# 04_-_CPU_-_PCIE_USB.net
KiCad netlist of a schematic drawn in Altium Designer
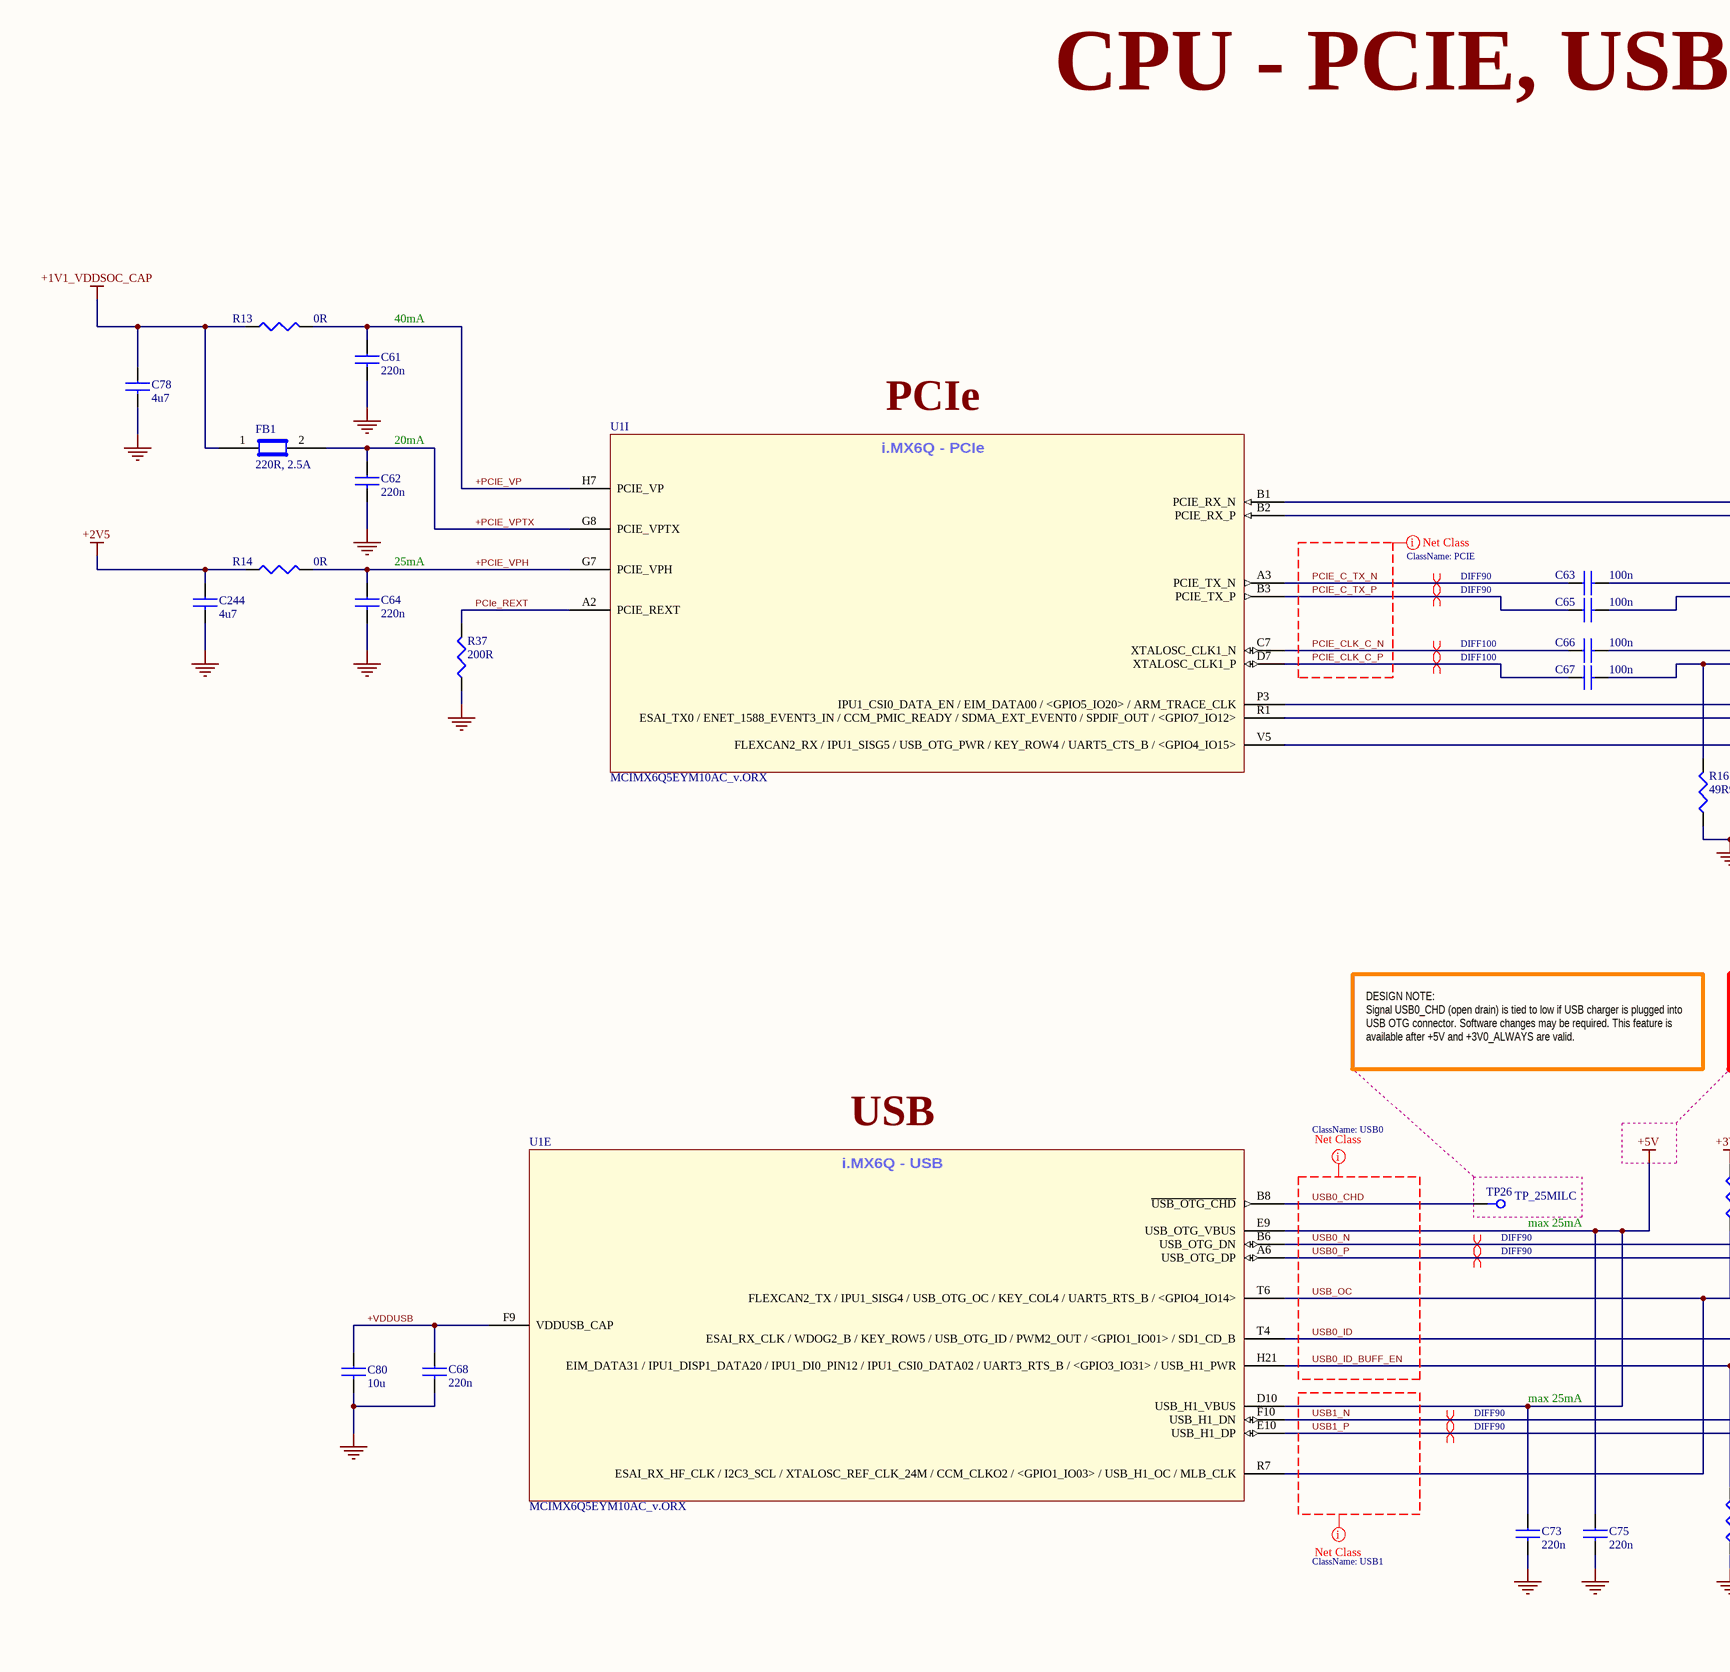
[diagram p0: [04] - CPU - PCIE, USB.SchDoc, left]
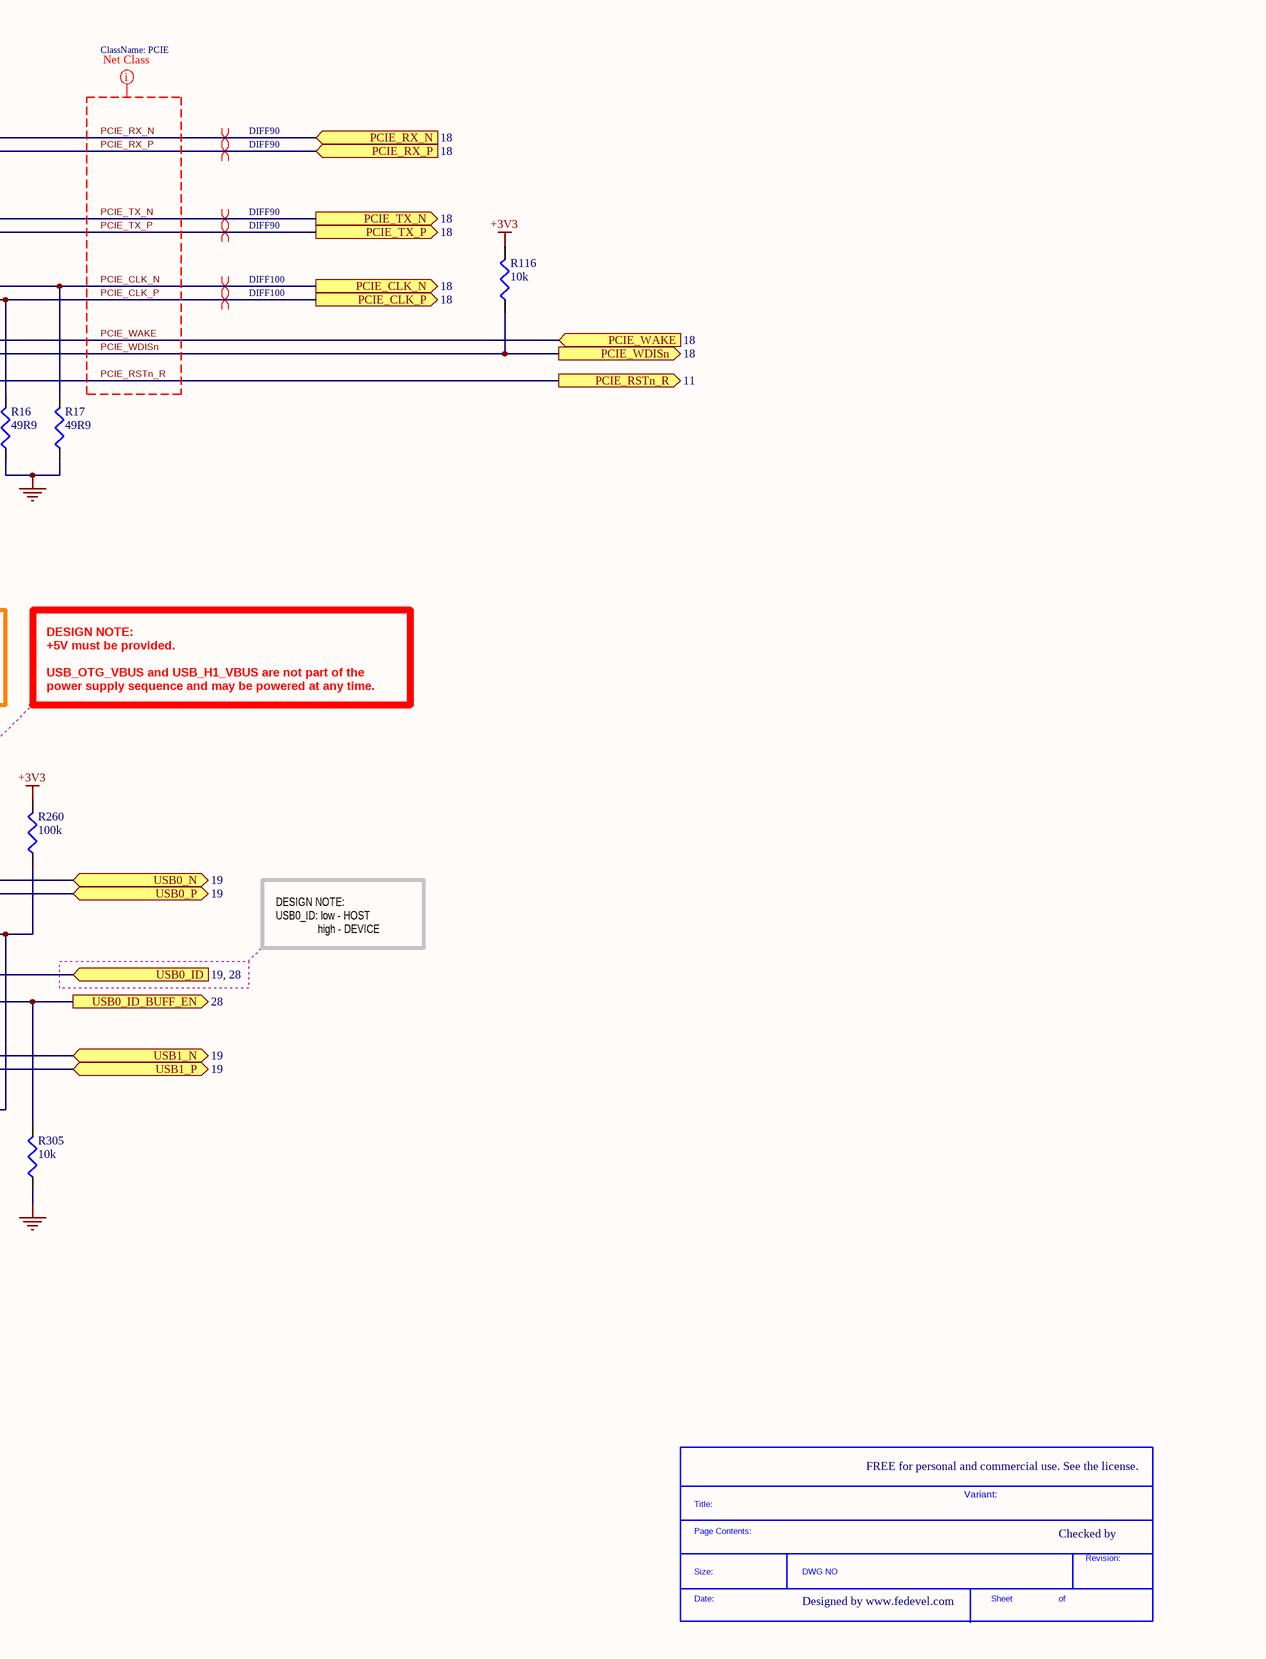
[diagram p1: [04] - CPU - PCIE, USB.SchDoc, right]

(export (version "E")
  (design (tool "Eeschema 10.0.6"))
  (components
    (comp (ref "C61")
      (value "220n")
      (footprint "C0201")
      (description "CAP CER 0.22UF 6.3V 20% X5R 0201")
      (fields
        (field (name "MANUFACTURER") "TDK Corporation")
        (field (name "MANUFACTURER PART NUMBER") "C0603X5R0J224M030BB")
        (field (name ".CHECKED PCB") "MM")
        (field (name ".CHECKED SCH") "MM")
        (field (name ".CREATOR") "MM")
      )
      (libsource (lib "Integrated_Library_FEDEVEL_0201") (part "C0603X5R0J224M030BB"))
    )
    (comp (ref "C62")
      (value "220n")
      (footprint "C0201")
      (description "CAP CER 0.22UF 6.3V 20% X5R 0201")
      (fields
        (field (name "MANUFACTURER") "TDK Corporation")
        (field (name "MANUFACTURER PART NUMBER") "C0603X5R0J224M030BB")
        (field (name ".CHECKED PCB") "MM")
        (field (name ".CHECKED SCH") "MM")
        (field (name ".CREATOR") "MM")
      )
      (libsource (lib "Integrated_Library_FEDEVEL_0201") (part "C0603X5R0J224M030BB"))
    )
    (comp (ref "C63")
      (value "100n")
      (footprint "C0402")
      (description "CAP CER .10UF 50V X5R 10% 0402")
      (fields
        (field (name "MANUFACTURER") "TDK Corporation")
        (field (name "MANUFACTURER PART NUMBER") "C1005X5R1H104K")
      )
      (libsource (lib "Integrated_Library_FEDEVEL_APR_2015") (part "C1005X5R1H104K"))
    )
    (comp (ref "C64")
      (value "220n")
      (footprint "C0201")
      (description "CAP CER 0.22UF 6.3V 20% X5R 0201")
      (fields
        (field (name "MANUFACTURER") "TDK Corporation")
        (field (name "MANUFACTURER PART NUMBER") "C0603X5R0J224M030BB")
        (field (name ".CHECKED PCB") "MM")
        (field (name ".CHECKED SCH") "MM")
        (field (name ".CREATOR") "MM")
      )
      (libsource (lib "Integrated_Library_FEDEVEL_0201") (part "C0603X5R0J224M030BB"))
    )
    (comp (ref "C65")
      (value "100n")
      (footprint "C0402")
      (description "CAP CER .10UF 50V X5R 10% 0402")
      (fields
        (field (name "MANUFACTURER") "TDK Corporation")
        (field (name "MANUFACTURER PART NUMBER") "C1005X5R1H104K")
      )
      (libsource (lib "Integrated_Library_FEDEVEL_APR_2015") (part "C1005X5R1H104K"))
    )
    (comp (ref "C66")
      (value "100n")
      (footprint "C0402")
      (description "CAP CER .10UF 50V X5R 10% 0402")
      (fields
        (field (name "MANUFACTURER") "TDK Corporation")
        (field (name "MANUFACTURER PART NUMBER") "C1005X5R1H104K")
      )
      (libsource (lib "Integrated_Library_FEDEVEL_APR_2015") (part "C1005X5R1H104K"))
    )
    (comp (ref "C67")
      (value "100n")
      (footprint "C0402")
      (description "CAP CER .10UF 50V X5R 10% 0402")
      (fields
        (field (name "MANUFACTURER") "TDK Corporation")
        (field (name "MANUFACTURER PART NUMBER") "C1005X5R1H104K")
      )
      (libsource (lib "Integrated_Library_FEDEVEL_APR_2015") (part "C1005X5R1H104K"))
    )
    (comp (ref "C68")
      (value "220n")
      (footprint "C0201")
      (description "CAP CER 0.22UF 6.3V 20% X5R 0201")
      (fields
        (field (name "MANUFACTURER") "TDK Corporation")
        (field (name "MANUFACTURER PART NUMBER") "C0603X5R0J224M030BB")
        (field (name ".CHECKED PCB") "MM")
        (field (name ".CHECKED SCH") "MM")
        (field (name ".CREATOR") "MM")
      )
      (libsource (lib "Integrated_Library_FEDEVEL_0201") (part "C0603X5R0J224M030BB"))
    )
    (comp (ref "C73")
      (value "220n")
      (footprint "C0201")
      (description "CAP CER 0.22UF 6.3V 20% X5R 0201")
      (fields
        (field (name "MANUFACTURER") "TDK Corporation")
        (field (name "MANUFACTURER PART NUMBER") "C0603X5R0J224M030BB")
        (field (name ".CHECKED PCB") "MM")
        (field (name ".CHECKED SCH") "MM")
        (field (name ".CREATOR") "MM")
      )
      (libsource (lib "Integrated_Library_FEDEVEL_0201") (part "C0603X5R0J224M030BB"))
    )
    (comp (ref "C75")
      (value "220n")
      (footprint "C0201")
      (description "CAP CER 0.22UF 6.3V 20% X5R 0201")
      (fields
        (field (name "MANUFACTURER") "TDK Corporation")
        (field (name "MANUFACTURER PART NUMBER") "C0603X5R0J224M030BB")
        (field (name ".CHECKED PCB") "MM")
        (field (name ".CHECKED SCH") "MM")
        (field (name ".CREATOR") "MM")
      )
      (libsource (lib "Integrated_Library_FEDEVEL_0201") (part "C0603X5R0J224M030BB"))
    )
    (comp (ref "C78")
      (value "4u7")
      (footprint "C0402")
      (description "CAP CER 4.7UF 10V 20% X5R 0402")
      (fields
        (field (name "MANUFACTURER") "TDK Corporation")
        (field (name "MANUFACTURER PART NUMBER") "C1005X5R1A475M")
      )
      (libsource (lib "Integrated_Library_FEDEVEL_APR_2015") (part "C1005X5R1A475M"))
    )
    (comp (ref "C80")
      (value "10u")
      (footprint "C0603")
      (description "CAP CER 10UF 6.3V X5R 20% 0603")
      (fields
        (field (name "MANUFACTURER") "TDK Corporation")
        (field (name "MANUFACTURER PART NUMBER") "C1608X5R0J106M")
      )
      (libsource (lib "Integrated_Library_FEDEVEL_APR_2015") (part "C1608X5R0J106M"))
    )
    (comp (ref "C244")
      (value "4u7")
      (footprint "C0402")
      (description "CAP CER 4.7UF 10V 20% X5R 0402")
      (fields
        (field (name "MANUFACTURER") "TDK Corporation")
        (field (name "MANUFACTURER PART NUMBER") "C1005X5R1A475M")
      )
      (libsource (lib "Integrated_Library_FEDEVEL_APR_2015") (part "C1005X5R1A475M"))
    )
    (comp (ref "FB1")
      (value "220R, 2.5A")
      (footprint "C0603")
      (description "FERRITE CHIP 220 OHM 2500MA 0603")
      (fields
        (field (name "MANUFACTURER") "Murata Electronics North America")
        (field (name "MANUFACTURER PART NUMBER") "BLM18SG221TN1D")
      )
      (libsource (lib "Integrated_Library_FEDEVEL_APR_2015") (part "BLM18SG221TN1D"))
    )
    (comp (ref "R13")
      (value "0R")
      (footprint "R0402")
      (description "RES 0.0 OHM 1/16W 0402 SMD")
      (fields
        (field (name "MANUFACTURER") "Yageo")
        (field (name "MANUFACTURER PART NUMBER") "RC0402JR-070RL")
      )
      (libsource (lib "Integrated_Library_FEDEVEL_APR_2015") (part "RC0402JR-070RL"))
    )
    (comp (ref "R14")
      (value "0R")
      (footprint "R0402")
      (description "RES 0.0 OHM 1/16W 0402 SMD")
      (fields
        (field (name "MANUFACTURER") "Yageo")
        (field (name "MANUFACTURER PART NUMBER") "RC0402JR-070RL")
      )
      (libsource (lib "Integrated_Library_FEDEVEL_APR_2015") (part "RC0402JR-070RL"))
    )
    (comp (ref "R16")
      (value "49R9")
      (footprint "R0402")
      (description "RES 49.9 OHM 1/16W 1% 0402 SMD")
      (fields
        (field (name "MANUFACTURER") "Yageo")
        (field (name "MANUFACTURER PART NUMBER") "RC0402FR-0749R9L")
      )
      (libsource (lib "Integrated_Library_FEDEVEL_APR_2015") (part "RC0402FR-0749R9L"))
    )
    (comp (ref "R17")
      (value "49R9")
      (footprint "R0402")
      (description "RES 49.9 OHM 1/16W 1% 0402 SMD")
      (fields
        (field (name "MANUFACTURER") "Yageo")
        (field (name "MANUFACTURER PART NUMBER") "RC0402FR-0749R9L")
      )
      (libsource (lib "Integrated_Library_FEDEVEL_APR_2015") (part "RC0402FR-0749R9L"))
    )
    (comp (ref "R37")
      (value "200R")
      (footprint "R0402")
      (description "RES 200 OHM 1/16W 1% 0402 SMD")
      (fields
        (field (name "MANUFACTURER") "Vishay Dale")
        (field (name "MANUFACTURER PART NUMBER") "CRCW0402200RFKED")
        (field (name ".CREATOR") "MM")
      )
      (libsource (lib "Integrated_Library_FEDEVEL_APR_2015") (part "CRCW0402200RFKED"))
    )
    (comp (ref "R116")
      (value "10k")
      (footprint "R0402")
      (description "RES 10.0K OHM 1/16W 1% 0402 SMD")
      (fields
        (field (name "MANUFACTURER") "Yageo")
        (field (name "MANUFACTURER PART NUMBER") "RC0402FR-0710KL")
      )
      (libsource (lib "Integrated_Library_FEDEVEL_APR_2015") (part "RC0402FR-0710KL"))
    )
    (comp (ref "R260")
      (value "100k")
      (footprint "R0201")
      (description "RES 100K OHM 1/20W 1% 0201 SMD")
      (fields
        (field (name "MANUFACTURER") "Yageo")
        (field (name "MANUFACTURER PART NUMBER") "RC0201FR-07100KL")
        (field (name ".CREATOR") "MM")
        (field (name ".CHECKED PCB") "MM")
        (field (name ".CHECKED SCH") "MM")
      )
      (libsource (lib "Integrated_Library_FEDEVEL_0201") (part "RC0201FR-07100KL"))
    )
    (comp (ref "R305")
      (value "10k")
      (footprint "R0402")
      (description "RES 10.0K OHM 1/16W 1% 0402 SMD")
      (fields
        (field (name "MANUFACTURER") "Yageo")
        (field (name "MANUFACTURER PART NUMBER") "RC0402FR-0710KL")
      )
      (libsource (lib "Integrated_Library_FEDEVEL_APR_2015") (part "RC0402FR-0710KL"))
    )
    (comp (ref "TP26")
      (value "TP_25MILC")
      (footprint "TP_25C")
      (description "Test Point 25mil")
      (libsource (lib "Integrated_Library_FEDEVEL_APR_2015") (part "TP_25MILC"))
    )
    (comp (ref "U1")
      (value "MCIMX6Q5EYM10AC_v.ORX")
      (footprint "PBGA624")
      (description "IC MCU 32BIT ARM QUAD 624FCBGA")
      (fields
        (field (name "MANUFACTURER") "Freescale Semiconductor")
        (field (name "MANUFACTURER PART NUMBER") "MCIMX6Q5EYM10AC")
        (field (name ".CREATOR") "MM")
        (field (name ".CHECKED PCB") "MM, checked by RF")
      )
      (libsource (lib "Integrated_Library_FEDEVEL_APR_2015") (part "MCIMX6Q5EYM10AC_v.ORX"))
    )
  )
  (nets
    (net (code "1") (name "+1V1_VDDSOC_CAP") (class "Default")
      (node (ref "C78") (pin "1") (pinfunction "1_1") (pintype "passive"))
      (node (ref "FB1") (pin "1") (pinfunction "1_1") (pintype "passive"))
      (node (ref "R13") (pin "1") (pinfunction "1_1") (pintype "passive"))
    )
    (net (code "2") (name "+2V5") (class "Default")
      (node (ref "C244") (pin "1") (pinfunction "1_1") (pintype "passive"))
      (node (ref "R14") (pin "1") (pinfunction "1_1") (pintype "passive"))
    )
    (net (code "3") (name "+3V3") (class "Default")
      (node (ref "R116") (pin "2") (pinfunction "2_2") (pintype "passive"))
      (node (ref "R260") (pin "2") (pinfunction "2_2") (pintype "passive"))
    )
    (net (code "4") (name "+5V") (class "Default")
      (node (ref "C73") (pin "1") (pinfunction "1_1") (pintype "passive"))
      (node (ref "C75") (pin "1") (pinfunction "1_1") (pintype "passive"))
      (node (ref "U1") (pin "D10") (pinfunction "USB_H1_VBUS_D10") (pintype "power_in"))
      (node (ref "U1") (pin "E9") (pinfunction "USB_OTG_VBUS_E9") (pintype "power_in"))
    )
    (net (code "5") (name "/+PCIE_VP") (class "Default")
      (node (ref "C61") (pin "1") (pinfunction "1_1") (pintype "passive"))
      (node (ref "R13") (pin "2") (pinfunction "2_2") (pintype "passive"))
      (node (ref "U1") (pin "H7") (pinfunction "PCIE_VP_H7") (pintype "power_in"))
    )
    (net (code "6") (name "/+PCIE_VPH") (class "Default")
      (node (ref "C64") (pin "1") (pinfunction "1_1") (pintype "passive"))
      (node (ref "R14") (pin "2") (pinfunction "2_2") (pintype "passive"))
      (node (ref "U1") (pin "G7") (pinfunction "PCIE_VPH_G7") (pintype "power_in"))
    )
    (net (code "7") (name "/+PCIE_VPTX") (class "Default")
      (node (ref "C62") (pin "1") (pinfunction "1_1") (pintype "passive"))
      (node (ref "FB1") (pin "2") (pinfunction "2_2") (pintype "passive"))
      (node (ref "U1") (pin "G8") (pinfunction "PCIE_VPTX_G8") (pintype "power_in"))
    )
    (net (code "8") (name "/+VDDUSB") (class "Default")
      (node (ref "C68") (pin "1") (pinfunction "1_1") (pintype "passive"))
      (node (ref "C80") (pin "1") (pinfunction "1_1") (pintype "passive"))
      (node (ref "U1") (pin "F9") (pinfunction "VDDUSB_CAP_F9") (pintype "power_in"))
    )
    (net (code "9") (name "/PCIE_CLK_C_N") (class "Default")
      (node (ref "C66") (pin "1") (pinfunction "1_1") (pintype "passive"))
      (node (ref "U1") (pin "C7") (pinfunction "XTALOSC_CLK1_N_C7") (pintype "bidirectional"))
    )
    (net (code "10") (name "/PCIE_CLK_C_P") (class "Default")
      (node (ref "C67") (pin "1") (pinfunction "1_1") (pintype "passive"))
      (node (ref "U1") (pin "D7") (pinfunction "XTALOSC_CLK1_P_D7") (pintype "bidirectional"))
    )
    (net (code "11") (name "/PCIE_CLK_N") (class "Default")
      (node (ref "C66") (pin "2") (pinfunction "2_2") (pintype "passive"))
      (node (ref "R17") (pin "2") (pinfunction "2_2") (pintype "passive"))
    )
    (net (code "12") (name "/PCIE_CLK_P") (class "Default")
      (node (ref "C67") (pin "2") (pinfunction "2_2") (pintype "passive"))
      (node (ref "R16") (pin "2") (pinfunction "2_2") (pintype "passive"))
    )
    (net (code "13") (name "/PCIE_C_TX_N") (class "Default")
      (node (ref "C63") (pin "1") (pinfunction "1_1") (pintype "passive"))
      (node (ref "U1") (pin "A3") (pinfunction "PCIE_TX_N_A3") (pintype "output"))
    )
    (net (code "14") (name "/PCIE_C_TX_P") (class "Default")
      (node (ref "C65") (pin "1") (pinfunction "1_1") (pintype "passive"))
      (node (ref "U1") (pin "B3") (pinfunction "PCIE_TX_P_B3") (pintype "output"))
    )
    (net (code "15") (name "/PCIE_RSTn_R") (class "Default")
      (node (ref "U1") (pin "V5") (pinfunction "FLEXCAN2_RX_/_IPU1_SISG5_/_USB_OTG_PWR_/_KEY_ROW4_/_UART5_CTS_B_/_<GPIO4_IO15>_V5") (pintype "passive"))
    )
    (net (code "16") (name "/PCIE_RX_N") (class "Default")
      (node (ref "U1") (pin "B1") (pinfunction "PCIE_RX_N_B1") (pintype "input"))
    )
    (net (code "17") (name "/PCIE_RX_P") (class "Default")
      (node (ref "U1") (pin "B2") (pinfunction "PCIE_RX_P_B2") (pintype "input"))
    )
    (net (code "18") (name "/PCIE_TX_N") (class "Default")
      (node (ref "C63") (pin "2") (pinfunction "2_2") (pintype "passive"))
    )
    (net (code "19") (name "/PCIE_TX_P") (class "Default")
      (node (ref "C65") (pin "2") (pinfunction "2_2") (pintype "passive"))
    )
    (net (code "20") (name "/PCIE_WAKE") (class "Default")
      (node (ref "U1") (pin "P3") (pinfunction "IPU1_CSI0_DATA_EN_/_EIM_DATA00_/_<GPIO5_IO20>_/_ARM_TRACE_CLK_P3") (pintype "passive"))
    )
    (net (code "21") (name "/PCIE_WDISn") (class "Default")
      (node (ref "R116") (pin "1") (pinfunction "1_1") (pintype "passive"))
      (node (ref "U1") (pin "R1") (pinfunction "ESAI_TX0_/_ENET_1588_EVENT3_IN_/_CCM_PMIC_READY_/_SDMA_EXT_EVENT0_/_SPDIF_OUT_/_<GPIO7_IO12>_R1") (pintype "passive"))
    )
    (net (code "22") (name "/PCIe_REXT") (class "Default")
      (node (ref "R37") (pin "2") (pinfunction "2_2") (pintype "passive"))
      (node (ref "U1") (pin "A2") (pinfunction "PCIE_REXT_A2") (pintype "passive"))
    )
    (net (code "23") (name "/USB0_CHD") (class "Default")
      (node (ref "TP26") (pin "1") (pinfunction "1_1") (pintype "passive"))
      (node (ref "U1") (pin "B8") (pinfunction "~{USB_OTG_CHD}_B8") (pintype "output"))
    )
    (net (code "24") (name "/USB0_ID") (class "Default")
      (node (ref "U1") (pin "T4") (pinfunction "ESAI_RX_CLK_/_WDOG2_B_/_KEY_ROW5_/_USB_OTG_ID_/_PWM2_OUT_/_<GPIO1_IO01>_/_SD1_CD_B_T4") (pintype "passive"))
    )
    (net (code "25") (name "/USB0_ID_BUFF_EN") (class "Default")
      (node (ref "R305") (pin "2") (pinfunction "2_2") (pintype "passive"))
      (node (ref "U1") (pin "H21") (pinfunction "EIM_DATA31_/_IPU1_DISP1_DATA20_/_IPU1_DI0_PIN12_/_IPU1_CSI0_DATA02_/_UART3_RTS_B_/_<GPIO3_IO31>_/_USB_H1_PWR_H21") (pintype "passive"))
    )
    (net (code "26") (name "/USB0_N") (class "Default")
      (node (ref "U1") (pin "B6") (pinfunction "USB_OTG_DN_B6") (pintype "bidirectional"))
    )
    (net (code "27") (name "/USB0_P") (class "Default")
      (node (ref "U1") (pin "A6") (pinfunction "USB_OTG_DP_A6") (pintype "bidirectional"))
    )
    (net (code "28") (name "/USB1_N") (class "Default")
      (node (ref "U1") (pin "F10") (pinfunction "USB_H1_DN_F10") (pintype "bidirectional"))
    )
    (net (code "29") (name "/USB1_P") (class "Default")
      (node (ref "U1") (pin "E10") (pinfunction "USB_H1_DP_E10") (pintype "bidirectional"))
    )
    (net (code "30") (name "/USB_OC") (class "Default")
      (node (ref "R260") (pin "1") (pinfunction "1_1") (pintype "passive"))
      (node (ref "U1") (pin "R7") (pinfunction "ESAI_RX_HF_CLK_/_I2C3_SCL_/_XTALOSC_REF_CLK_24M_/_CCM_CLKO2_/_<GPIO1_IO03>_/_USB_H1_OC_/_MLB_CLK_R7") (pintype "passive"))
      (node (ref "U1") (pin "T6") (pinfunction "FLEXCAN2_TX_/_IPU1_SISG4_/_USB_OTG_OC_/_KEY_COL4_/_UART5_RTS_B_/_<GPIO4_IO14>_T6") (pintype "passive"))
    )
    (net (code "31") (name "GND") (class "Default")
      (node (ref "C244") (pin "2") (pinfunction "2_2") (pintype "passive"))
      (node (ref "C61") (pin "2") (pinfunction "2_2") (pintype "passive"))
      (node (ref "C62") (pin "2") (pinfunction "2_2") (pintype "passive"))
      (node (ref "C64") (pin "2") (pinfunction "2_2") (pintype "passive"))
      (node (ref "C68") (pin "2") (pinfunction "2_2") (pintype "passive"))
      (node (ref "C73") (pin "2") (pinfunction "2_2") (pintype "passive"))
      (node (ref "C75") (pin "2") (pinfunction "2_2") (pintype "passive"))
      (node (ref "C78") (pin "2") (pinfunction "2_2") (pintype "passive"))
      (node (ref "C80") (pin "2") (pinfunction "2_2") (pintype "passive"))
      (node (ref "R16") (pin "1") (pinfunction "1_1") (pintype "passive"))
      (node (ref "R17") (pin "1") (pinfunction "1_1") (pintype "passive"))
      (node (ref "R305") (pin "1") (pinfunction "1_1") (pintype "passive"))
      (node (ref "R37") (pin "1") (pinfunction "1_1") (pintype "passive"))
    )
  )
)
